# MUDE.net
KiCad netlist of a schematic drawn in EAGLE
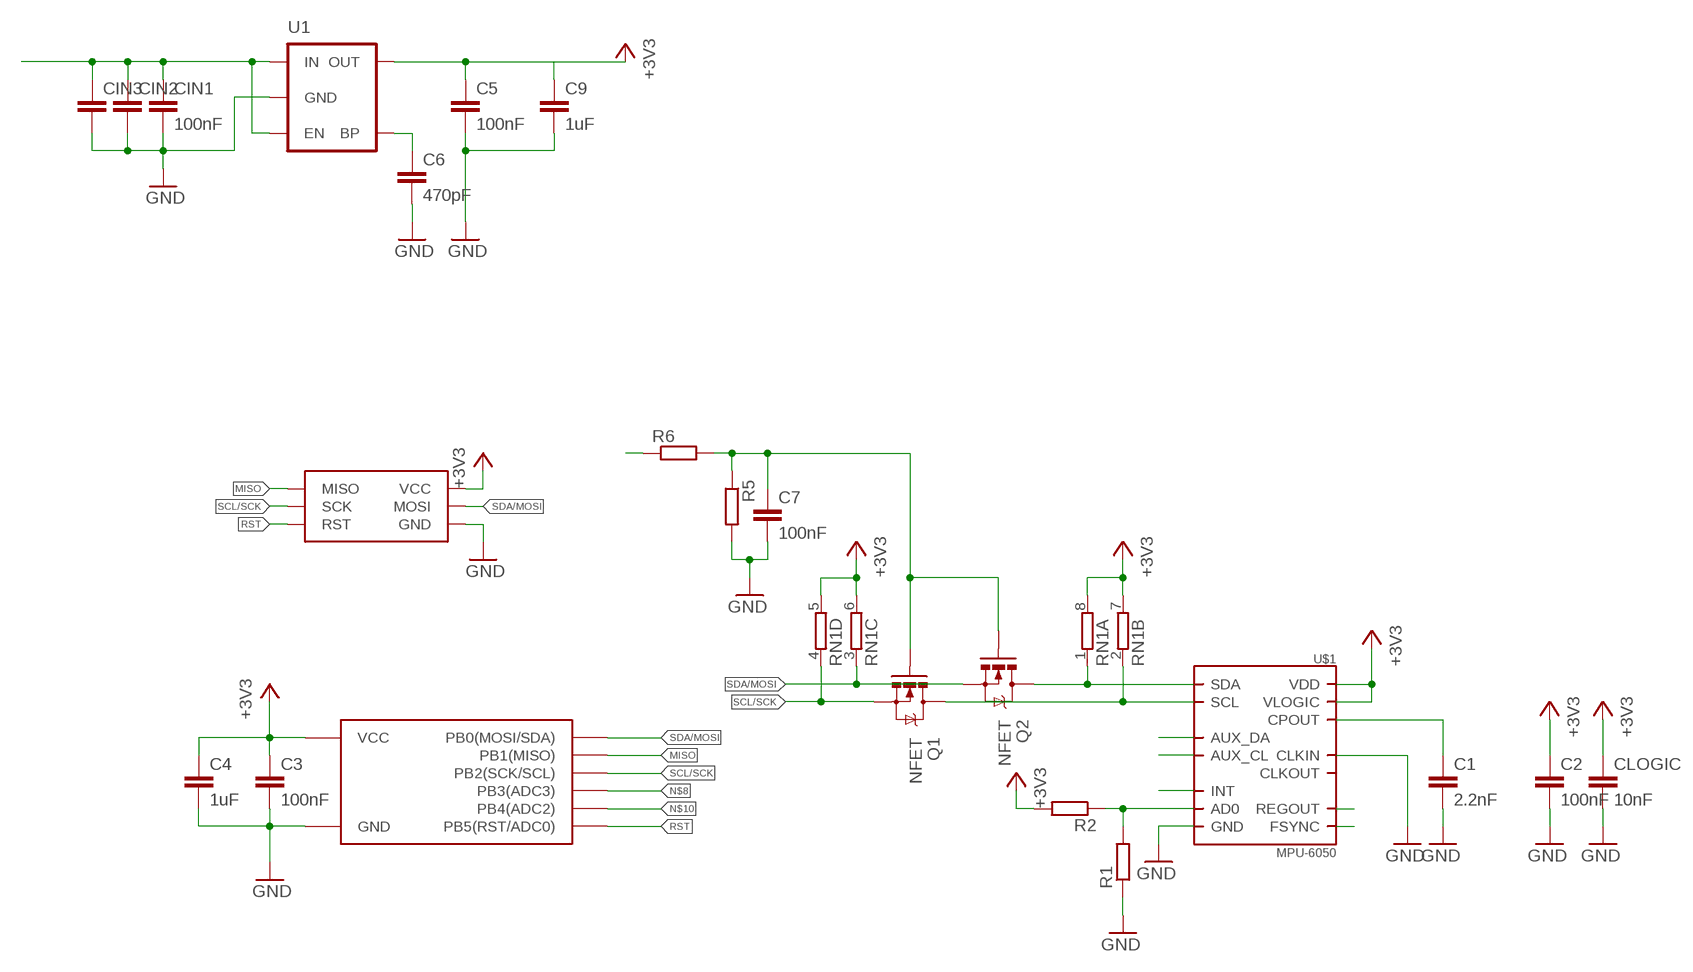
[diagram p0: schematic, sheet 1]

(export (version "E")
  (design (tool "Eeschema 10.0.6"))
  (components
    (comp (ref "C1")
      (value "2.2nF")
      (footprint "eagle-import:C0603")
      (libsource (lib "eagle-import") (part "C-EUC0603"))
    )
    (comp (ref "C2")
      (value "100nF")
      (footprint "eagle-import:C0603")
      (libsource (lib "eagle-import") (part "C-EUC0603"))
    )
    (comp (ref "C3")
      (value "100nF")
      (footprint "eagle-import:C0603")
      (libsource (lib "eagle-import") (part "C-EUC0603"))
    )
    (comp (ref "C4")
      (value "1uF")
      (footprint "eagle-import:C0603")
      (libsource (lib "eagle-import") (part "C-EUC0603"))
    )
    (comp (ref "C5")
      (value "100nF")
      (footprint "eagle-import:C0603")
      (libsource (lib "eagle-import") (part "C-EUC0603"))
    )
    (comp (ref "C6")
      (value "470pF")
      (footprint "eagle-import:C0603")
      (libsource (lib "eagle-import") (part "C-EUC0603"))
    )
    (comp (ref "C7")
      (value "100nF")
      (footprint "eagle-import:C0603")
      (libsource (lib "eagle-import") (part "C-EUC0603"))
    )
    (comp (ref "C9")
      (value "1uF")
      (footprint "eagle-import:C0603")
      (libsource (lib "eagle-import") (part "C-EUC0603"))
    )
    (comp (ref "CIN1")
      (value "100nF")
      (footprint "eagle-import:C0603")
      (libsource (lib "eagle-import") (part "C-EUC0603"))
    )
    (comp (ref "CIN2")
      (value "C-EUC0805")
      (footprint "eagle-import:C0805")
      (libsource (lib "eagle-import") (part "C-EUC0805"))
    )
    (comp (ref "CIN3")
      (value "C-EUC0805")
      (footprint "eagle-import:C0805")
      (libsource (lib "eagle-import") (part "C-EUC0805"))
    )
    (comp (ref "CLOGIC")
      (value "10nF")
      (footprint "eagle-import:C0603")
      (libsource (lib "eagle-import") (part "C-EUC0603"))
    )
    (comp (ref "Q1")
      (value "NFET")
      (footprint "eagle-import:SOT23")
      (libsource (lib "eagle-import") (part "MOSFET-NCHANNELBSS123LT1G"))
    )
    (comp (ref "Q2")
      (value "NFET")
      (footprint "eagle-import:SOT23")
      (libsource (lib "eagle-import") (part "MOSFET-NCHANNELBSS123LT1G"))
    )
    (comp (ref "R1")
      (value "R-EU_R0603")
      (footprint "eagle-import:R0603")
      (libsource (lib "eagle-import") (part "R-EU_R0603"))
    )
    (comp (ref "R2")
      (value "R-EU_R0603")
      (footprint "eagle-import:R0603")
      (libsource (lib "eagle-import") (part "R-EU_R0603"))
    )
    (comp (ref "R5")
      (value "R-EU_R0603")
      (footprint "eagle-import:R0603")
      (libsource (lib "eagle-import") (part "R-EU_R0603"))
    )
    (comp (ref "R6")
      (value "R-EU_R0603")
      (footprint "eagle-import:R0603")
      (libsource (lib "eagle-import") (part "R-EU_R0603"))
    )
    (comp (ref "RN1")
      (value "4R-N0603-ARV")
      (footprint "eagle-import:0603-ARV")
      (libsource (lib "eagle-import") (part "4R-N0603-ARV"))
    )
    (comp (ref "U$1")
      (value "MPU-6050")
      (footprint "eagle-import:QFN.24.4X4")
      (libsource (lib "eagle-import") (part "MPU-6050"))
    )
    (comp (ref "U$2")
      (value "ATTINY45")
      (footprint "eagle-import:QFN20")
      (libsource (lib "eagle-import") (part "ATTINY45"))
    )
    (comp (ref "U$3")
      (value "ISP_POGOISP_POGO")
      (footprint "eagle-import:ISP_POGO")
      (libsource (lib "eagle-import") (part "ISP_POGOISP_POGO"))
    )
    (comp (ref "U1")
      (value "MIC52053.3V")
      (footprint "eagle-import:SOT23-5")
      (libsource (lib "eagle-import") (part "MIC52053.3V"))
    )
  )
  (nets
    (net (code "1") (name "+3V3") (class "Default")
      (node (ref "C2") (pin "1") (pinfunction "1_1") (pintype "passive"))
      (node (ref "C3") (pin "1") (pinfunction "1_1") (pintype "passive"))
      (node (ref "C4") (pin "1") (pinfunction "1_1") (pintype "passive"))
      (node (ref "C5") (pin "1") (pinfunction "1_1") (pintype "passive"))
      (node (ref "C9") (pin "1") (pinfunction "1_1") (pintype "passive"))
      (node (ref "CLOGIC") (pin "1") (pinfunction "1_1") (pintype "passive"))
      (node (ref "R2") (pin "2") (pinfunction "2_2") (pintype "passive"))
      (node (ref "RN1") (pin "5") (pinfunction "2_5") (pintype "passive"))
      (node (ref "RN1") (pin "6") (pinfunction "2_6") (pintype "passive"))
      (node (ref "RN1") (pin "7") (pinfunction "2_7") (pintype "passive"))
      (node (ref "RN1") (pin "8") (pinfunction "2_8") (pintype "passive"))
      (node (ref "U$1") (pin "13") (pinfunction "VDD_13") (pintype "bidirectional"))
      (node (ref "U$1") (pin "8") (pinfunction "VLOGIC_8") (pintype "bidirectional"))
      (node (ref "U$2") (pin "P$15") (pinfunction "VCC_P$15") (pintype "bidirectional"))
      (node (ref "U$3") (pin "VCC") (pinfunction "VCC_VCC") (pintype "bidirectional"))
      (node (ref "U1") (pin "5") (pinfunction "OUT_5") (pintype "passive"))
    )
    (net (code "2") (name "GND") (class "Default")
      (node (ref "C1") (pin "2") (pinfunction "2_2") (pintype "passive"))
      (node (ref "C2") (pin "2") (pinfunction "2_2") (pintype "passive"))
      (node (ref "C3") (pin "2") (pinfunction "2_2") (pintype "passive"))
      (node (ref "C4") (pin "2") (pinfunction "2_2") (pintype "passive"))
      (node (ref "C5") (pin "2") (pinfunction "2_2") (pintype "passive"))
      (node (ref "C6") (pin "2") (pinfunction "2_2") (pintype "passive"))
      (node (ref "C7") (pin "2") (pinfunction "2_2") (pintype "passive"))
      (node (ref "C9") (pin "2") (pinfunction "2_2") (pintype "passive"))
      (node (ref "CIN1") (pin "2") (pinfunction "2_2") (pintype "passive"))
      (node (ref "CIN2") (pin "2") (pinfunction "2_2") (pintype "passive"))
      (node (ref "CIN3") (pin "2") (pinfunction "2_2") (pintype "passive"))
      (node (ref "CLOGIC") (pin "2") (pinfunction "2_2") (pintype "passive"))
      (node (ref "R1") (pin "1") (pinfunction "1_1") (pintype "passive"))
      (node (ref "R5") (pin "2") (pinfunction "2_2") (pintype "passive"))
      (node (ref "U$1") (pin "1") (pinfunction "CLKIN_1") (pintype "bidirectional"))
      (node (ref "U$1") (pin "18") (pinfunction "GND_18") (pintype "bidirectional"))
      (node (ref "U$2") (pin "P$8") (pinfunction "GND_P$8") (pintype "bidirectional"))
      (node (ref "U$2") (pin "PAD") (pinfunction "GND_PAD") (pintype "bidirectional"))
      (node (ref "U$3") (pin "GND") (pinfunction "GND_GND") (pintype "bidirectional"))
      (node (ref "U1") (pin "2") (pinfunction "GND_2") (pintype "input"))
    )
    (net (code "3") (name "MISO") (class "Default")
      (node (ref "U$2") (pin "P$12") (pinfunction "PB1(MISO)_P$12") (pintype "bidirectional"))
      (node (ref "U$3") (pin "MISO") (pinfunction "MISO_MISO") (pintype "bidirectional"))
    )
    (net (code "4") (name "N$8") (class "Default")
      (node (ref "U$2") (pin "P$2") (pinfunction "PB3(ADC3)_P$2") (pintype "bidirectional"))
    )
    (net (code "5") (name "N$10") (class "Default")
      (node (ref "U$2") (pin "P$5") (pinfunction "PB4(ADC2)_P$5") (pintype "bidirectional"))
    )
    (net (code "6") (name "Net-(Q1-D)") (class "Default")
      (node (ref "Q1") (pin "3") (pinfunction "D_3") (pintype "passive"))
      (node (ref "RN1") (pin "2") (pinfunction "1_2") (pintype "passive"))
      (node (ref "U$1") (pin "23") (pinfunction "SCL_23") (pintype "bidirectional"))
    )
    (net (code "7") (name "Net-(Q1-G)") (class "Default")
      (node (ref "C7") (pin "1") (pinfunction "1_1") (pintype "passive"))
      (node (ref "Q1") (pin "1") (pinfunction "G_1") (pintype "passive"))
      (node (ref "Q2") (pin "1") (pinfunction "G_1") (pintype "passive"))
      (node (ref "R5") (pin "1") (pinfunction "1_1") (pintype "passive"))
      (node (ref "R6") (pin "2") (pinfunction "2_2") (pintype "passive"))
    )
    (net (code "8") (name "Net-(Q2-D)") (class "Default")
      (node (ref "Q2") (pin "3") (pinfunction "D_3") (pintype "passive"))
      (node (ref "RN1") (pin "1") (pinfunction "1_1") (pintype "passive"))
      (node (ref "U$1") (pin "24") (pinfunction "SDA_24") (pintype "bidirectional"))
    )
    (net (code "9") (name "Net-(U$1-AD0)") (class "Default")
      (node (ref "R1") (pin "2") (pinfunction "2_2") (pintype "passive"))
      (node (ref "R2") (pin "1") (pinfunction "1_1") (pintype "passive"))
      (node (ref "U$1") (pin "9") (pinfunction "AD0_9") (pintype "bidirectional"))
    )
    (net (code "10") (name "Net-(U$1-CPOUT)") (class "Default")
      (node (ref "C1") (pin "1") (pinfunction "1_1") (pintype "passive"))
      (node (ref "U$1") (pin "20") (pinfunction "CPOUT_20") (pintype "bidirectional"))
    )
    (net (code "11") (name "Net-(U1-BP)") (class "Default")
      (node (ref "C6") (pin "1") (pinfunction "1_1") (pintype "passive"))
      (node (ref "U1") (pin "4") (pinfunction "BP_4") (pintype "input"))
    )
    (net (code "12") (name "Net-(U1-EN)") (class "Default")
      (node (ref "CIN1") (pin "1") (pinfunction "1_1") (pintype "passive"))
      (node (ref "CIN2") (pin "1") (pinfunction "1_1") (pintype "passive"))
      (node (ref "CIN3") (pin "1") (pinfunction "1_1") (pintype "passive"))
      (node (ref "U1") (pin "1") (pinfunction "IN_1") (pintype "input"))
      (node (ref "U1") (pin "3") (pinfunction "EN_3") (pintype "input"))
    )
    (net (code "13") (name "RST") (class "Default")
      (node (ref "U$2") (pin "P$1") (pinfunction "PB5(RST/ADC0)_P$1") (pintype "bidirectional"))
      (node (ref "U$3") (pin "RST") (pinfunction "RST_RST") (pintype "bidirectional"))
    )
    (net (code "14") (name "SCL{slash}SCK") (class "Default")
      (node (ref "Q1") (pin "2") (pinfunction "S_2") (pintype "passive"))
      (node (ref "RN1") (pin "4") (pinfunction "1_4") (pintype "passive"))
      (node (ref "U$2") (pin "P$14") (pinfunction "PB2(SCK/SCL)_P$14") (pintype "bidirectional"))
      (node (ref "U$3") (pin "SCK") (pinfunction "SCK_SCK") (pintype "bidirectional"))
    )
    (net (code "15") (name "SDA{slash}MOSI") (class "Default")
      (node (ref "Q2") (pin "2") (pinfunction "S_2") (pintype "passive"))
      (node (ref "RN1") (pin "3") (pinfunction "1_3") (pintype "passive"))
      (node (ref "U$2") (pin "P$11") (pinfunction "PB0(MOSI/SDA)_P$11") (pintype "bidirectional"))
      (node (ref "U$3") (pin "MOSI") (pinfunction "MOSI_MOSI") (pintype "bidirectional"))
    )
    (net (code "16") (name "unconnected-(R6-Pad1)") (class "Default")
      (node (ref "R6") (pin "1") (pinfunction "1_1") (pintype "passive"))
    )
    (net (code "17") (name "unconnected-(U$1-AUX_CL-Pad7)") (class "Default")
      (node (ref "U$1") (pin "7") (pinfunction "AUX_CL_7") (pintype "bidirectional"))
    )
    (net (code "18") (name "unconnected-(U$1-AUX_DA-Pad6)") (class "Default")
      (node (ref "U$1") (pin "6") (pinfunction "AUX_DA_6") (pintype "bidirectional"))
    )
    (net (code "19") (name "unconnected-(U$1-CLKOUT-Pad22)") (class "Default")
      (node (ref "U$1") (pin "22") (pinfunction "CLKOUT_22") (pintype "bidirectional"))
    )
    (net (code "20") (name "unconnected-(U$1-FSYNC-Pad11)") (class "Default")
      (node (ref "U$1") (pin "11") (pinfunction "FSYNC_11") (pintype "bidirectional"))
    )
    (net (code "21") (name "unconnected-(U$1-INT-Pad12)") (class "Default")
      (node (ref "U$1") (pin "12") (pinfunction "INT_12") (pintype "bidirectional"))
    )
    (net (code "22") (name "unconnected-(U$1-REGOUT-Pad10)") (class "Default")
      (node (ref "U$1") (pin "10") (pinfunction "REGOUT_10") (pintype "bidirectional"))
    )
  )
)
